# SOM_JX_MIO.net
KiCad netlist of a schematic drawn in Altium Designer
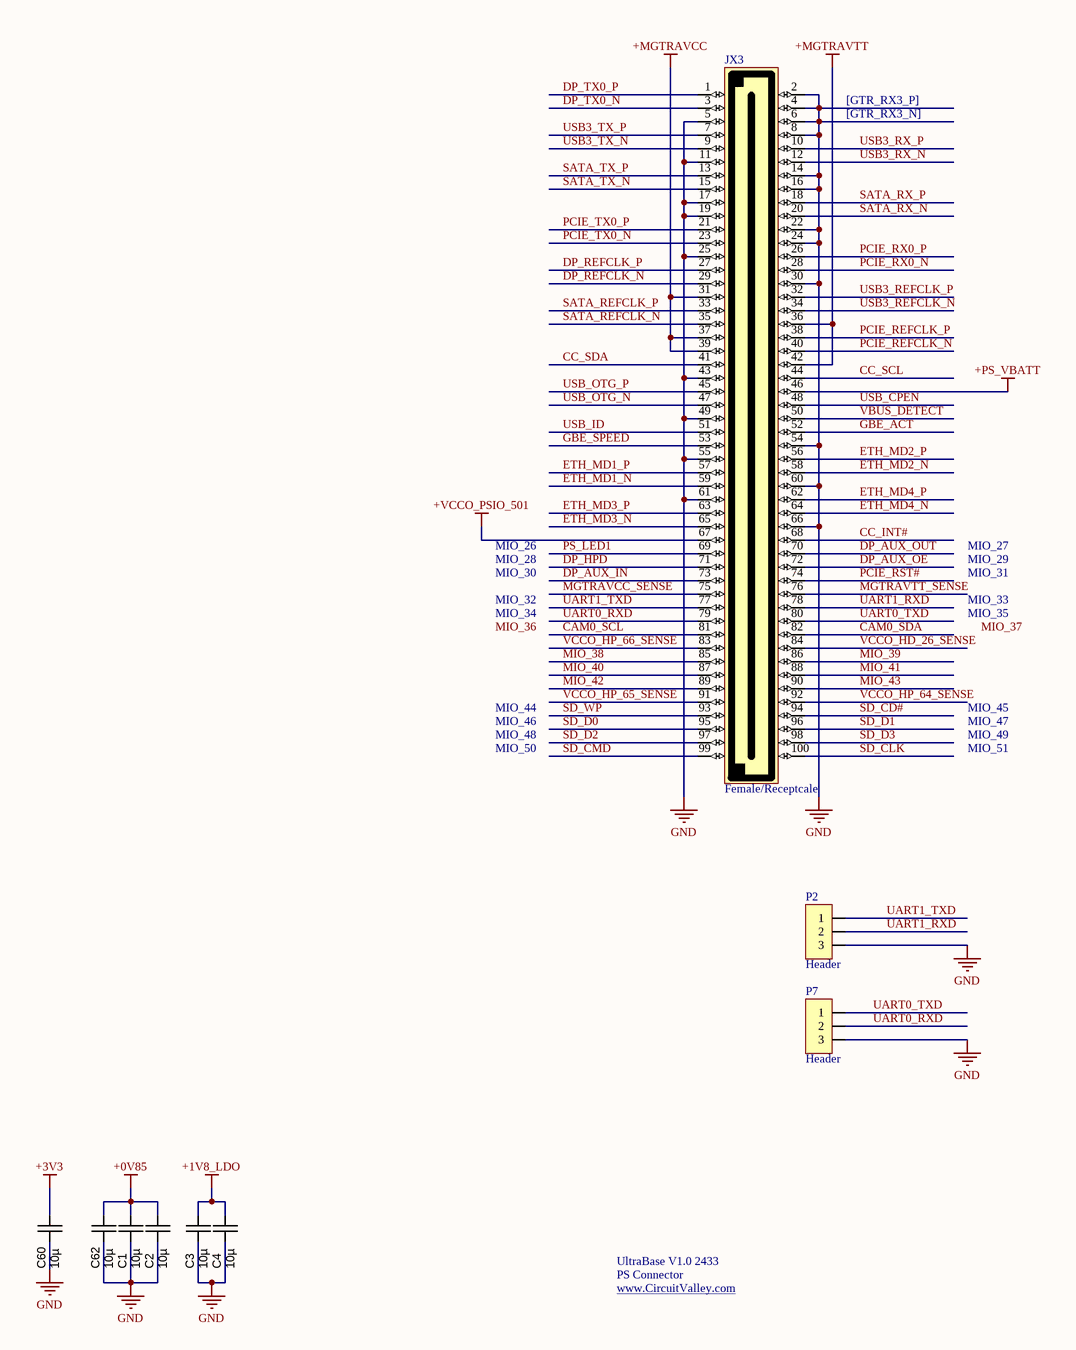
[diagram p0: SOM_JX_MIO.SchDoc]

(export (version "E")
  (design (tool "Eeschema 10.0.6"))
  (components
    (comp (ref "C1")
      (value "10µ")
      (footprint "CAPC3225N")
      (description "Capacitor SMD Cer 10uF 20% 16V X5R 1210")
      (fields (field (name "TOLERANCE") "±20%"))
      (libsource (lib "PBL - Capacitors") (part "CAPC_10u_1210_50V"))
    )
    (comp (ref "C2")
      (value "10µ")
      (footprint "CAPC3225N")
      (description "Capacitor SMD Cer 10uF 20% 16V X5R 1210")
      (fields (field (name "TOLERANCE") "±20%"))
      (libsource (lib "PBL - Capacitors") (part "CAPC_10u_1210_50V"))
    )
    (comp (ref "C3")
      (value "10µ")
      (footprint "CAPC3225N")
      (description "Capacitor SMD Cer 10uF 20% 16V X5R 1210")
      (fields (field (name "TOLERANCE") "±20%"))
      (libsource (lib "PBL - Capacitors") (part "CAPC_10u_1210_50V"))
    )
    (comp (ref "C4")
      (value "10µ")
      (footprint "CAPC3225N")
      (description "Capacitor SMD Cer 10uF 20% 16V X5R 1210")
      (fields (field (name "TOLERANCE") "±20%"))
      (libsource (lib "PBL - Capacitors") (part "CAPC_10u_1210_50V"))
    )
    (comp (ref "C60")
      (value "10µ")
      (footprint "CAPC3225N")
      (description "Capacitor SMD Cer 10uF 20% 16V X5R 1210")
      (fields (field (name "TOLERANCE") "±20%"))
      (libsource (lib "PBL - Capacitors") (part "CAPC_10u_1210_50V"))
    )
    (comp (ref "C62")
      (value "10µ")
      (footprint "CAPC3225N")
      (description "Capacitor SMD Cer 10uF 20% 16V X5R 1210")
      (fields (field (name "TOLERANCE") "±20%"))
      (libsource (lib "PBL - Capacitors") (part "CAPC_10u_1210_50V"))
    )
    (comp (ref "JX3")
      (value "Female/Receptcale")
      (footprint "5177985-4")
      (description "100 Pin Ultrascale  SOM Connector with ultrazed specific SOM net delay")
      (libsource (lib "cvlib") (part "5177985-4_Ultrazed"))
    )
    (comp (ref "P2")
      (value "Header")
      (footprint "Header3x")
      (description "3 Pin Header")
      (libsource (lib "cvlib") (part "Header_3Pin"))
    )
    (comp (ref "P7")
      (value "Header")
      (footprint "Header3x")
      (description "3 Pin Header")
      (libsource (lib "cvlib") (part "Header_3Pin"))
    )
  )
  (nets
    (net (code "1") (name "+0V85") (class "Default")
      (node (ref "C1") (pin "1") (pintype "passive"))
      (node (ref "C2") (pin "1") (pintype "passive"))
      (node (ref "C62") (pin "1") (pintype "passive"))
    )
    (net (code "2") (name "+1V8_LDO") (class "Default")
      (node (ref "C3") (pin "1") (pintype "passive"))
      (node (ref "C4") (pin "1") (pintype "passive"))
    )
    (net (code "3") (name "+3V3") (class "Default") (node (ref "C60") (pin "1") (pintype "passive")))
    (net (code "4") (name "+MGTRAVCC") (class "Default")
      (node (ref "JX3") (pin "31") (pintype "bidirectional"))
      (node (ref "JX3") (pin "37") (pintype "bidirectional"))
      (node (ref "JX3") (pin "39") (pintype "bidirectional"))
    )
    (net (code "5") (name "+MGTRAVTT") (class "Default")
      (node (ref "JX3") (pin "36") (pintype "bidirectional"))
      (node (ref "JX3") (pin "42") (pintype "bidirectional"))
    )
    (net (code "6") (name "+PS_VBATT") (class "Default")
      (node (ref "JX3") (pin "46") (pintype "bidirectional"))
    )
    (net (code "7") (name "+VCCO_PSIO_501") (class "Default")
      (node (ref "JX3") (pin "67") (pintype "bidirectional"))
    )
    (net (code "8") (name "/CAM0_SCL") (class "Default")
      (node (ref "JX3") (pin "81") (pintype "bidirectional"))
    )
    (net (code "9") (name "/CAM0_SDA") (class "Default")
      (node (ref "JX3") (pin "82") (pintype "bidirectional"))
    )
    (net (code "10") (name "/CC_INT#") (class "Default")
      (node (ref "JX3") (pin "68") (pintype "bidirectional"))
    )
    (net (code "11") (name "/CC_SCL") (class "Default")
      (node (ref "JX3") (pin "44") (pintype "bidirectional"))
    )
    (net (code "12") (name "/CC_SDA") (class "Default")
      (node (ref "JX3") (pin "41") (pintype "bidirectional"))
    )
    (net (code "13") (name "/DP_AUX_IN") (class "Default")
      (node (ref "JX3") (pin "73") (pintype "bidirectional"))
    )
    (net (code "14") (name "/DP_AUX_OE") (class "Default")
      (node (ref "JX3") (pin "72") (pintype "bidirectional"))
    )
    (net (code "15") (name "/DP_AUX_OUT") (class "Default")
      (node (ref "JX3") (pin "70") (pintype "bidirectional"))
    )
    (net (code "16") (name "/DP_HPD") (class "Default")
      (node (ref "JX3") (pin "71") (pintype "bidirectional"))
    )
    (net (code "17") (name "/DP_REFCLK_N") (class "Default")
      (node (ref "JX3") (pin "29") (pintype "bidirectional"))
    )
    (net (code "18") (name "/DP_REFCLK_P") (class "Default")
      (node (ref "JX3") (pin "27") (pintype "bidirectional"))
    )
    (net (code "19") (name "/DP_TX0_N") (class "Default")
      (node (ref "JX3") (pin "3") (pintype "bidirectional"))
    )
    (net (code "20") (name "/DP_TX0_P") (class "Default")
      (node (ref "JX3") (pin "1") (pintype "bidirectional"))
    )
    (net (code "21") (name "/ETH_MD1_N") (class "Default")
      (node (ref "JX3") (pin "59") (pintype "bidirectional"))
    )
    (net (code "22") (name "/ETH_MD1_P") (class "Default")
      (node (ref "JX3") (pin "57") (pintype "bidirectional"))
    )
    (net (code "23") (name "/ETH_MD2_N") (class "Default")
      (node (ref "JX3") (pin "58") (pintype "bidirectional"))
    )
    (net (code "24") (name "/ETH_MD2_P") (class "Default")
      (node (ref "JX3") (pin "56") (pintype "bidirectional"))
    )
    (net (code "25") (name "/ETH_MD3_N") (class "Default")
      (node (ref "JX3") (pin "65") (pintype "bidirectional"))
    )
    (net (code "26") (name "/ETH_MD3_P") (class "Default")
      (node (ref "JX3") (pin "63") (pintype "bidirectional"))
    )
    (net (code "27") (name "/ETH_MD4_N") (class "Default")
      (node (ref "JX3") (pin "64") (pintype "bidirectional"))
    )
    (net (code "28") (name "/ETH_MD4_P") (class "Default")
      (node (ref "JX3") (pin "62") (pintype "bidirectional"))
    )
    (net (code "29") (name "/GBE_ACT") (class "Default")
      (node (ref "JX3") (pin "52") (pintype "bidirectional"))
    )
    (net (code "30") (name "/GBE_SPEED") (class "Default")
      (node (ref "JX3") (pin "53") (pintype "bidirectional"))
    )
    (net (code "31") (name "/MGTRAVCC_SENSE") (class "Default")
      (node (ref "JX3") (pin "75") (pintype "bidirectional"))
    )
    (net (code "32") (name "/MGTRAVTT_SENSE") (class "Default")
      (node (ref "JX3") (pin "76") (pintype "bidirectional"))
    )
    (net (code "35") (name "/MIO_38") (class "Default")
      (node (ref "JX3") (pin "85") (pintype "bidirectional"))
    )
    (net (code "36") (name "/MIO_39") (class "Default")
      (node (ref "JX3") (pin "86") (pintype "bidirectional"))
    )
    (net (code "37") (name "/MIO_40") (class "Default")
      (node (ref "JX3") (pin "87") (pintype "bidirectional"))
    )
    (net (code "38") (name "/MIO_41") (class "Default")
      (node (ref "JX3") (pin "88") (pintype "bidirectional"))
    )
    (net (code "39") (name "/MIO_42") (class "Default")
      (node (ref "JX3") (pin "89") (pintype "bidirectional"))
    )
    (net (code "40") (name "/MIO_43") (class "Default")
      (node (ref "JX3") (pin "90") (pintype "bidirectional"))
    )
    (net (code "41") (name "/PCIE_REFCLK_N") (class "Default")
      (node (ref "JX3") (pin "40") (pintype "bidirectional"))
    )
    (net (code "42") (name "/PCIE_REFCLK_P") (class "Default")
      (node (ref "JX3") (pin "38") (pintype "bidirectional"))
    )
    (net (code "43") (name "/PCIE_RST#") (class "Default")
      (node (ref "JX3") (pin "74") (pintype "bidirectional"))
    )
    (net (code "44") (name "/PCIE_RX0_N") (class "Default")
      (node (ref "JX3") (pin "28") (pintype "bidirectional"))
    )
    (net (code "45") (name "/PCIE_RX0_P") (class "Default")
      (node (ref "JX3") (pin "26") (pintype "bidirectional"))
    )
    (net (code "46") (name "/PCIE_TX0_N") (class "Default")
      (node (ref "JX3") (pin "23") (pintype "bidirectional"))
    )
    (net (code "47") (name "/PCIE_TX0_P") (class "Default")
      (node (ref "JX3") (pin "21") (pintype "bidirectional"))
    )
    (net (code "48") (name "/PS_LED1") (class "Default")
      (node (ref "JX3") (pin "69") (pintype "bidirectional"))
    )
    (net (code "49") (name "/SATA_REFCLK_N") (class "Default")
      (node (ref "JX3") (pin "35") (pintype "bidirectional"))
    )
    (net (code "50") (name "/SATA_REFCLK_P") (class "Default")
      (node (ref "JX3") (pin "33") (pintype "bidirectional"))
    )
    (net (code "51") (name "/SATA_RX_N") (class "Default")
      (node (ref "JX3") (pin "20") (pintype "bidirectional"))
    )
    (net (code "52") (name "/SATA_RX_P") (class "Default")
      (node (ref "JX3") (pin "18") (pintype "bidirectional"))
    )
    (net (code "53") (name "/SATA_TX_N") (class "Default")
      (node (ref "JX3") (pin "15") (pintype "bidirectional"))
    )
    (net (code "54") (name "/SATA_TX_P") (class "Default")
      (node (ref "JX3") (pin "13") (pintype "bidirectional"))
    )
    (net (code "55") (name "/SD_CD#") (class "Default")
      (node (ref "JX3") (pin "94") (pintype "bidirectional"))
    )
    (net (code "56") (name "/SD_CLK") (class "Default")
      (node (ref "JX3") (pin "100") (pintype "bidirectional"))
    )
    (net (code "57") (name "/SD_CMD") (class "Default")
      (node (ref "JX3") (pin "99") (pintype "bidirectional"))
    )
    (net (code "58") (name "/SD_D0") (class "Default")
      (node (ref "JX3") (pin "95") (pintype "bidirectional"))
    )
    (net (code "59") (name "/SD_D1") (class "Default")
      (node (ref "JX3") (pin "96") (pintype "bidirectional"))
    )
    (net (code "60") (name "/SD_D2") (class "Default")
      (node (ref "JX3") (pin "97") (pintype "bidirectional"))
    )
    (net (code "61") (name "/SD_D3") (class "Default")
      (node (ref "JX3") (pin "98") (pintype "bidirectional"))
    )
    (net (code "62") (name "/SD_WP") (class "Default")
      (node (ref "JX3") (pin "93") (pintype "bidirectional"))
    )
    (net (code "63") (name "/UART0_RXD") (class "Default")
      (node (ref "JX3") (pin "79") (pintype "bidirectional"))
      (node (ref "P7") (pin "2") (pinfunction "2_2") (pintype "passive"))
    )
    (net (code "64") (name "/UART0_TXD") (class "Default")
      (node (ref "JX3") (pin "80") (pintype "bidirectional"))
      (node (ref "P7") (pin "1") (pinfunction "1_1") (pintype "passive"))
    )
    (net (code "65") (name "/UART1_RXD") (class "Default")
      (node (ref "JX3") (pin "78") (pintype "bidirectional"))
      (node (ref "P2") (pin "2") (pinfunction "2_2") (pintype "passive"))
    )
    (net (code "66") (name "/UART1_TXD") (class "Default")
      (node (ref "JX3") (pin "77") (pintype "bidirectional"))
      (node (ref "P2") (pin "1") (pinfunction "1_1") (pintype "passive"))
    )
    (net (code "67") (name "/USB3_REFCLK_N") (class "Default")
      (node (ref "JX3") (pin "34") (pintype "bidirectional"))
    )
    (net (code "68") (name "/USB3_REFCLK_P") (class "Default")
      (node (ref "JX3") (pin "32") (pintype "bidirectional"))
    )
    (net (code "69") (name "/USB3_RX_N") (class "Default")
      (node (ref "JX3") (pin "12") (pintype "bidirectional"))
    )
    (net (code "70") (name "/USB3_RX_P") (class "Default")
      (node (ref "JX3") (pin "10") (pintype "bidirectional"))
    )
    (net (code "71") (name "/USB3_TX_N") (class "Default")
      (node (ref "JX3") (pin "9") (pintype "bidirectional"))
    )
    (net (code "72") (name "/USB3_TX_P") (class "Default")
      (node (ref "JX3") (pin "7") (pintype "bidirectional"))
    )
    (net (code "73") (name "/USB_CPEN") (class "Default")
      (node (ref "JX3") (pin "48") (pintype "bidirectional"))
    )
    (net (code "74") (name "/USB_ID") (class "Default")
      (node (ref "JX3") (pin "51") (pintype "bidirectional"))
    )
    (net (code "75") (name "/USB_OTG_N") (class "Default")
      (node (ref "JX3") (pin "47") (pintype "bidirectional"))
    )
    (net (code "76") (name "/USB_OTG_P") (class "Default")
      (node (ref "JX3") (pin "45") (pintype "bidirectional"))
    )
    (net (code "77") (name "/VBUS_DETECT") (class "Default")
      (node (ref "JX3") (pin "50") (pintype "bidirectional"))
    )
    (net (code "78") (name "/VCCO_HD_26_SENSE") (class "Default")
      (node (ref "JX3") (pin "84") (pintype "bidirectional"))
    )
    (net (code "79") (name "/VCCO_HP_64_SENSE") (class "Default")
      (node (ref "JX3") (pin "92") (pintype "bidirectional"))
    )
    (net (code "80") (name "/VCCO_HP_65_SENSE") (class "Default")
      (node (ref "JX3") (pin "91") (pintype "bidirectional"))
    )
    (net (code "81") (name "/VCCO_HP_66_SENSE") (class "Default")
      (node (ref "JX3") (pin "83") (pintype "bidirectional"))
    )
    (net (code "82") (name "GND") (class "Default")
      (node (ref "C1") (pin "2") (pintype "passive"))
      (node (ref "C2") (pin "2") (pintype "passive"))
      (node (ref "C3") (pin "2") (pintype "passive"))
      (node (ref "C4") (pin "2") (pintype "passive"))
      (node (ref "C60") (pin "2") (pintype "passive"))
      (node (ref "C62") (pin "2") (pintype "passive"))
      (node (ref "JX3") (pin "11") (pintype "bidirectional"))
      (node (ref "JX3") (pin "14") (pintype "bidirectional"))
      (node (ref "JX3") (pin "16") (pintype "bidirectional"))
      (node (ref "JX3") (pin "17") (pintype "bidirectional"))
      (node (ref "JX3") (pin "19") (pintype "bidirectional"))
      (node (ref "JX3") (pin "2") (pintype "bidirectional"))
      (node (ref "JX3") (pin "22") (pintype "bidirectional"))
      (node (ref "JX3") (pin "24") (pintype "bidirectional"))
      (node (ref "JX3") (pin "25") (pintype "bidirectional"))
      (node (ref "JX3") (pin "30") (pintype "bidirectional"))
      (node (ref "JX3") (pin "4") (pintype "bidirectional"))
      (node (ref "JX3") (pin "43") (pintype "bidirectional"))
      (node (ref "JX3") (pin "49") (pintype "bidirectional"))
      (node (ref "JX3") (pin "5") (pintype "bidirectional"))
      (node (ref "JX3") (pin "54") (pintype "bidirectional"))
      (node (ref "JX3") (pin "55") (pintype "bidirectional"))
      (node (ref "JX3") (pin "6") (pintype "bidirectional"))
      (node (ref "JX3") (pin "60") (pintype "bidirectional"))
      (node (ref "JX3") (pin "61") (pintype "bidirectional"))
      (node (ref "JX3") (pin "66") (pintype "bidirectional"))
      (node (ref "JX3") (pin "8") (pintype "bidirectional"))
      (node (ref "P2") (pin "3") (pinfunction "3_3") (pintype "passive"))
      (node (ref "P7") (pin "3") (pinfunction "3_3") (pintype "passive"))
    )
  )
)
